# scu_board.net
KiCad netlist of a schematic drawn in EAGLE
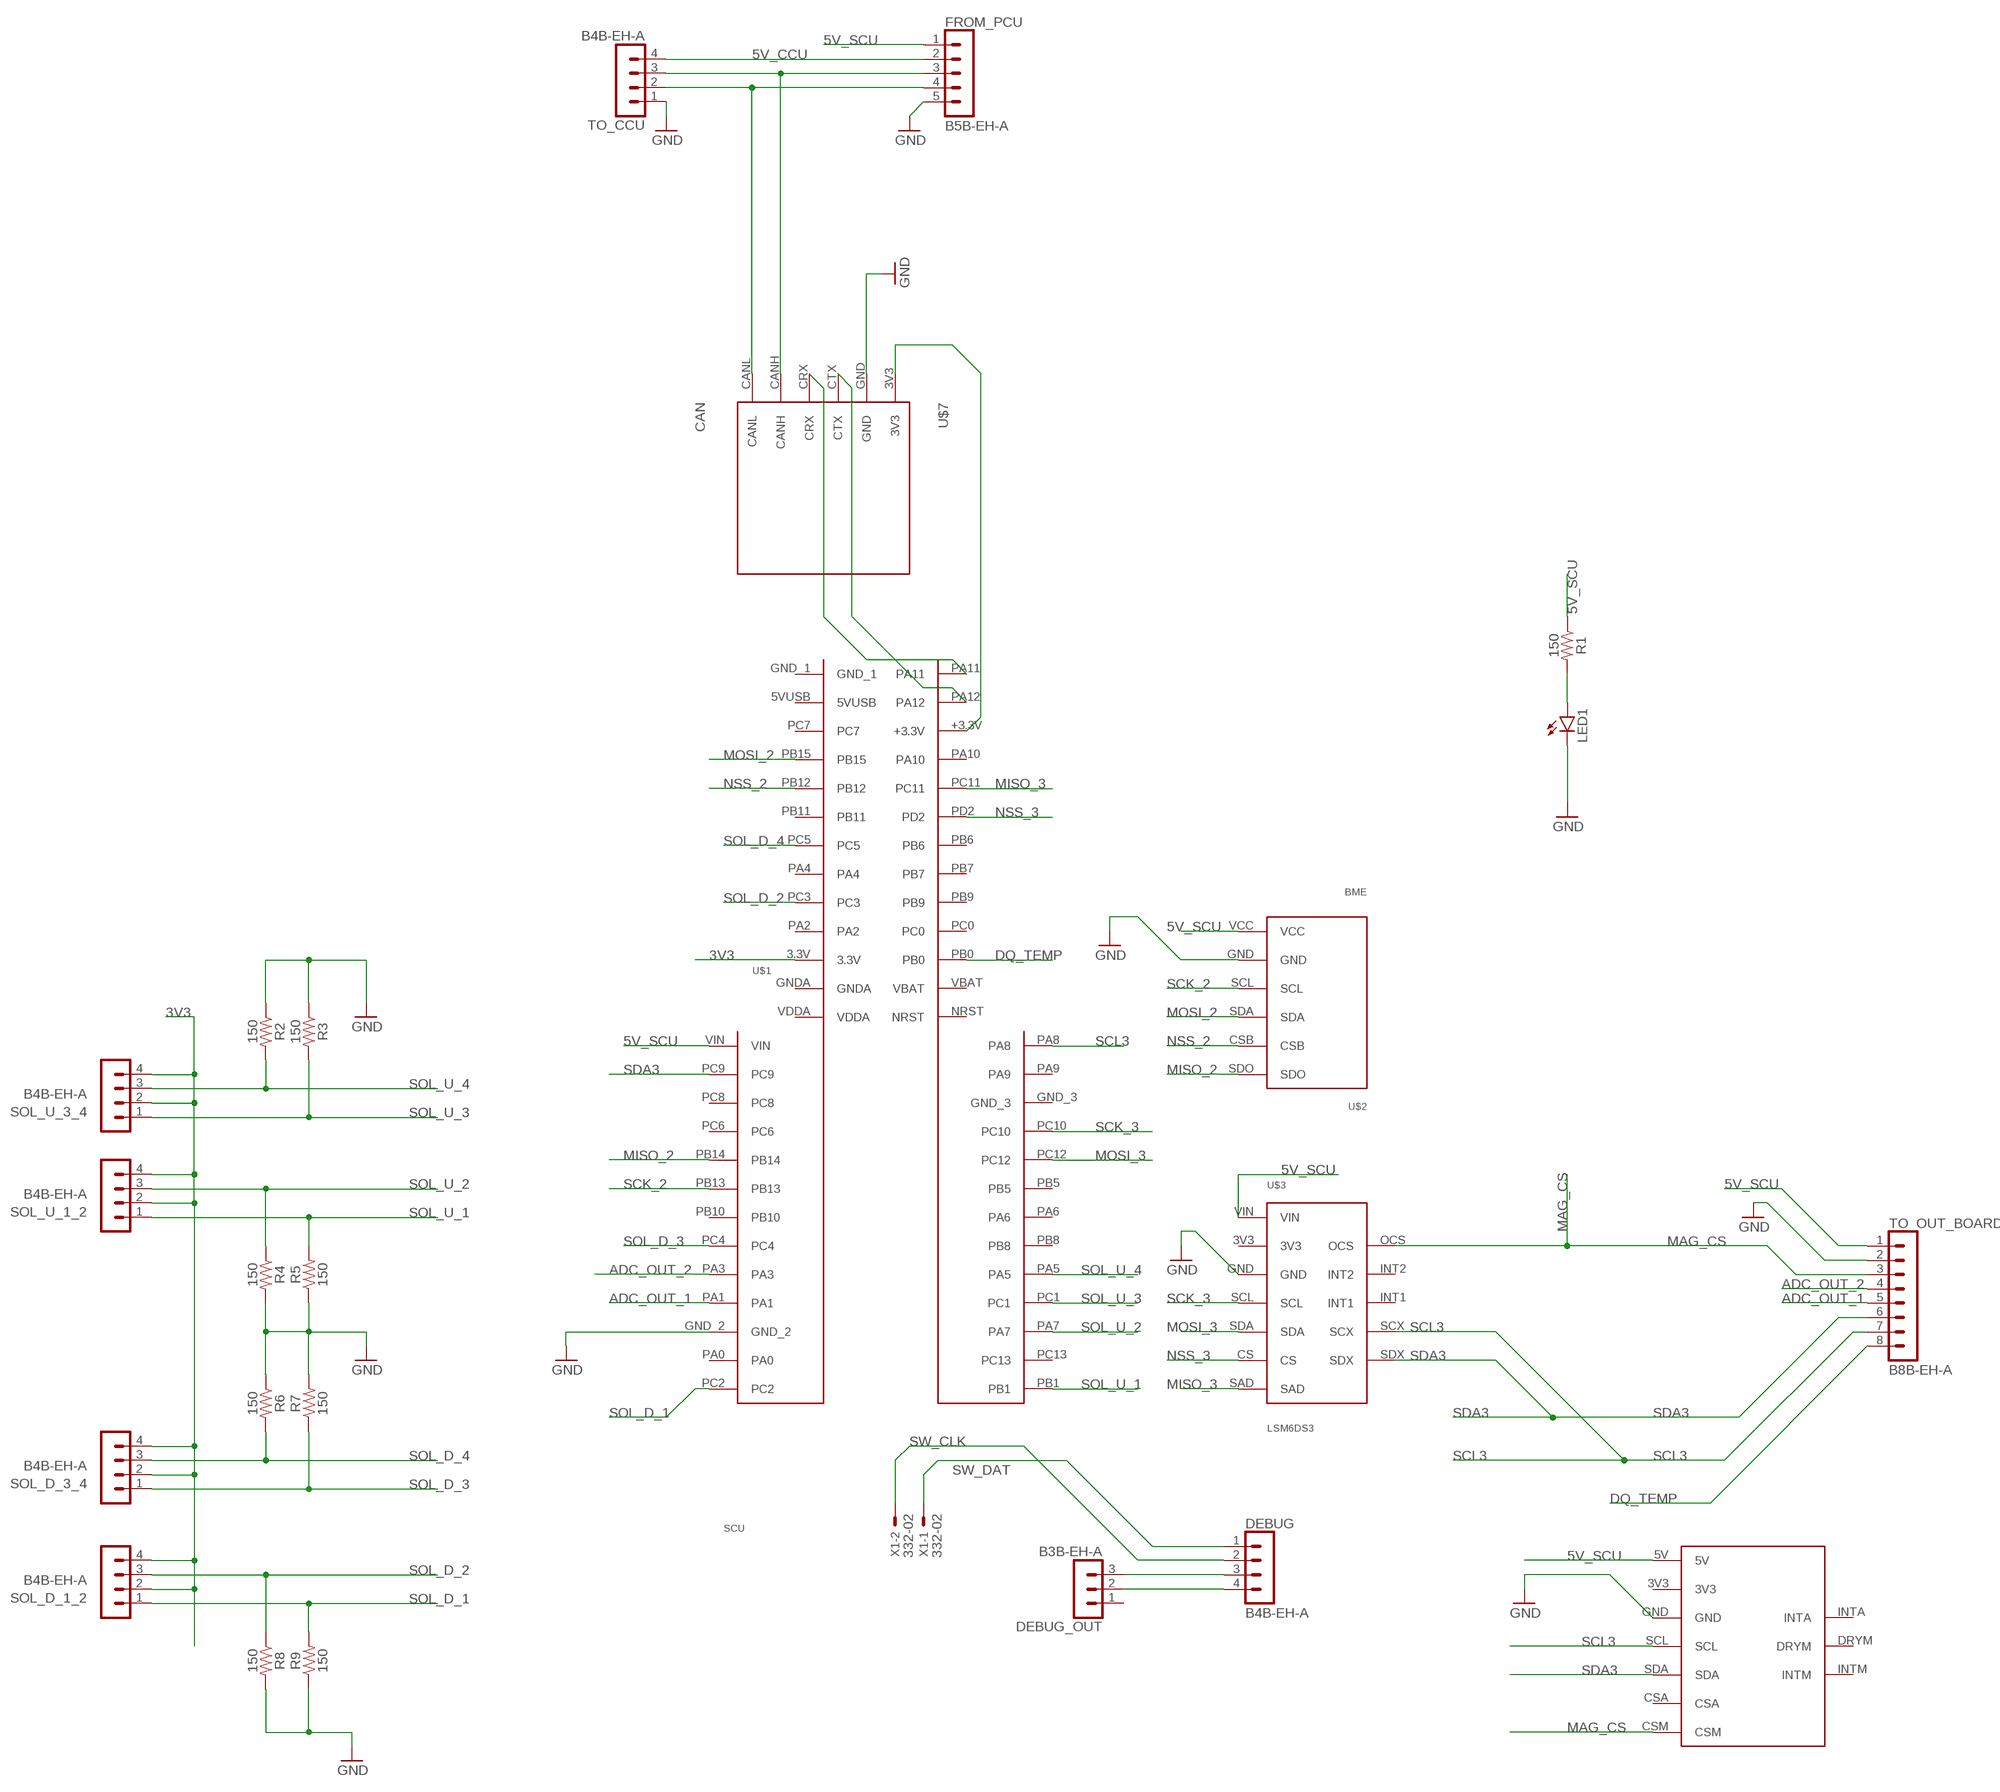
[diagram p0: schematic, sheet 1]

(export (version "E")
  (design (tool "Eeschema 10.0.6"))
  (components
    (comp (ref "DEBUG")
      (value "B4B-EH-A")
      (footprint "eagle-import:B4B-EH-A")
      (libsource (lib "eagle-import") (part "B4B-EH-A"))
    )
    (comp (ref "DEBUG_OUT")
      (value "B3B-EH-A")
      (footprint "eagle-import:B3B-EH-A")
      (libsource (lib "eagle-import") (part "B3B-EH-A"))
    )
    (comp (ref "FROM_PCU")
      (value "B5B-EH-A")
      (footprint "eagle-import:B5B-EH-A")
      (libsource (lib "eagle-import") (part "B5B-EH-A"))
    )
    (comp (ref "LED1")
      (value "LED5MM")
      (footprint "eagle-import:LED5MM")
      (libsource (lib "eagle-import") (part "LED5MM"))
    )
    (comp (ref "R1")
      (value "150")
      (footprint "eagle-import:AXIAL-0.3")
      (libsource (lib "eagle-import") (part "RESISTORAXIAL-0.3"))
    )
    (comp (ref "R2")
      (value "150")
      (footprint "eagle-import:AXIAL-0.3")
      (libsource (lib "eagle-import") (part "RESISTORAXIAL-0.3"))
    )
    (comp (ref "R3")
      (value "150")
      (footprint "eagle-import:AXIAL-0.3")
      (libsource (lib "eagle-import") (part "RESISTORAXIAL-0.3"))
    )
    (comp (ref "R4")
      (value "150")
      (footprint "eagle-import:AXIAL-0.3")
      (libsource (lib "eagle-import") (part "RESISTORAXIAL-0.3"))
    )
    (comp (ref "R5")
      (value "150")
      (footprint "eagle-import:AXIAL-0.3")
      (libsource (lib "eagle-import") (part "RESISTORAXIAL-0.3"))
    )
    (comp (ref "R6")
      (value "150")
      (footprint "eagle-import:AXIAL-0.3")
      (libsource (lib "eagle-import") (part "RESISTORAXIAL-0.3"))
    )
    (comp (ref "R7")
      (value "150")
      (footprint "eagle-import:AXIAL-0.3")
      (libsource (lib "eagle-import") (part "RESISTORAXIAL-0.3"))
    )
    (comp (ref "R8")
      (value "150")
      (footprint "eagle-import:AXIAL-0.3")
      (libsource (lib "eagle-import") (part "RESISTORAXIAL-0.3"))
    )
    (comp (ref "R9")
      (value "150")
      (footprint "eagle-import:AXIAL-0.3")
      (libsource (lib "eagle-import") (part "RESISTORAXIAL-0.3"))
    )
    (comp (ref "SOL_D_1_2")
      (value "B4B-EH-A")
      (footprint "eagle-import:B4B-EH-A")
      (libsource (lib "eagle-import") (part "B4B-EH-A"))
    )
    (comp (ref "SOL_D_3_4")
      (value "B4B-EH-A")
      (footprint "eagle-import:B4B-EH-A")
      (libsource (lib "eagle-import") (part "B4B-EH-A"))
    )
    (comp (ref "SOL_U_1_2")
      (value "B4B-EH-A")
      (footprint "eagle-import:B4B-EH-A")
      (libsource (lib "eagle-import") (part "B4B-EH-A"))
    )
    (comp (ref "SOL_U_3_4")
      (value "B4B-EH-A")
      (footprint "eagle-import:B4B-EH-A")
      (libsource (lib "eagle-import") (part "B4B-EH-A"))
    )
    (comp (ref "TO_CCU")
      (value "B4B-EH-A")
      (footprint "eagle-import:B4B-EH-A")
      (libsource (lib "eagle-import") (part "B4B-EH-A"))
    )
    (comp (ref "TO_OUT_BOARD")
      (value "B8B-EH-A")
      (footprint "eagle-import:B8B-EH-A")
      (libsource (lib "eagle-import") (part "B8B-EH-A"))
    )
    (comp (ref "U$1")
      (value "SCU")
      (footprint "eagle-import:SCU")
      (libsource (lib "eagle-import") (part "SCU"))
    )
    (comp (ref "U$2")
      (value "BME")
      (footprint "eagle-import:BME")
      (libsource (lib "eagle-import") (part "BME"))
    )
    (comp (ref "U$3")
      (value "LSM6DS3")
      (footprint "eagle-import:LSM6DS3")
      (libsource (lib "eagle-import") (part "LSM6DS3"))
    )
    (comp (ref "U$4")
      (value "LSM303C")
      (footprint "eagle-import:LSM303C")
      (libsource (lib "eagle-import") (part "LSM303C"))
    )
    (comp (ref "U$7")
      (value "CAN")
      (footprint "eagle-import:CAN")
      (libsource (lib "eagle-import") (part "CAN"))
    )
    (comp (ref "X1")
      (value "332-02")
      (footprint "eagle-import:332-02")
      (libsource (lib "eagle-import") (part "332-02"))
    )
  )
  (nets
    (net (code "1") (name "/3V3") (class "Default")
      (node (ref "SOL_D_1_2") (pin "2") (pinfunction "2_2") (pintype "passive"))
      (node (ref "SOL_D_1_2") (pin "4") (pinfunction "4_4") (pintype "passive"))
      (node (ref "SOL_D_3_4") (pin "2") (pinfunction "2_2") (pintype "passive"))
      (node (ref "SOL_D_3_4") (pin "4") (pinfunction "4_4") (pintype "passive"))
      (node (ref "SOL_U_1_2") (pin "2") (pinfunction "2_2") (pintype "passive"))
      (node (ref "SOL_U_1_2") (pin "4") (pinfunction "4_4") (pintype "passive"))
      (node (ref "SOL_U_3_4") (pin "2") (pinfunction "2_2") (pintype "passive"))
      (node (ref "SOL_U_3_4") (pin "4") (pinfunction "4_4") (pintype "passive"))
      (node (ref "U$1") (pin "3.3V") (pinfunction "3.3V_3.3V") (pintype "bidirectional"))
    )
    (net (code "2") (name "/5V_CCU") (class "Default")
      (node (ref "FROM_PCU") (pin "2") (pinfunction "2_2") (pintype "passive"))
      (node (ref "TO_CCU") (pin "4") (pinfunction "4_4") (pintype "passive"))
    )
    (net (code "3") (name "/5V_SCU") (class "Default")
      (node (ref "FROM_PCU") (pin "1") (pinfunction "1_1") (pintype "passive"))
      (node (ref "R1") (pin "P$1") (pinfunction "1_P$1") (pintype "passive"))
      (node (ref "TO_OUT_BOARD") (pin "1") (pinfunction "1_1") (pintype "passive"))
      (node (ref "U$1") (pin "VIN") (pinfunction "VIN_VIN") (pintype "bidirectional"))
      (node (ref "U$2") (pin "VCC") (pinfunction "VCC_VCC") (pintype "bidirectional"))
      (node (ref "U$3") (pin "VIN") (pinfunction "VIN_VIN") (pintype "bidirectional"))
      (node (ref "U$4") (pin "5V") (pinfunction "5V_5V") (pintype "bidirectional"))
    )
    (net (code "4") (name "/ADC_OUT_1") (class "Default")
      (node (ref "TO_OUT_BOARD") (pin "5") (pinfunction "5_5") (pintype "passive"))
      (node (ref "U$1") (pin "PA1") (pinfunction "PA1_PA1") (pintype "bidirectional"))
    )
    (net (code "5") (name "/ADC_OUT_2") (class "Default")
      (node (ref "TO_OUT_BOARD") (pin "4") (pinfunction "4_4") (pintype "passive"))
      (node (ref "U$1") (pin "PA3") (pinfunction "PA3_PA3") (pintype "bidirectional"))
    )
    (net (code "6") (name "/DQ_TEMP") (class "Default")
      (node (ref "TO_OUT_BOARD") (pin "8") (pinfunction "8_8") (pintype "passive"))
      (node (ref "U$1") (pin "PB0") (pinfunction "PB0_PB0") (pintype "bidirectional"))
    )
    (net (code "7") (name "/MAG_CS") (class "Default")
      (node (ref "TO_OUT_BOARD") (pin "3") (pinfunction "3_3") (pintype "passive"))
      (node (ref "U$3") (pin "OCS") (pinfunction "OCS_OCS") (pintype "bidirectional"))
      (node (ref "U$4") (pin "CSM") (pinfunction "CSM_CSM") (pintype "bidirectional"))
    )
    (net (code "8") (name "/MISO_2") (class "Default")
      (node (ref "U$1") (pin "PB14") (pinfunction "PB14_PB14") (pintype "bidirectional"))
      (node (ref "U$2") (pin "SDO") (pinfunction "SDO_SDO") (pintype "bidirectional"))
    )
    (net (code "9") (name "/MISO_3") (class "Default")
      (node (ref "U$1") (pin "PC11") (pinfunction "PC11_PC11") (pintype "bidirectional"))
      (node (ref "U$3") (pin "SAD") (pinfunction "SAD_SAD") (pintype "bidirectional"))
    )
    (net (code "10") (name "/MOSI_2") (class "Default")
      (node (ref "U$1") (pin "PB15") (pinfunction "PB15_PB15") (pintype "bidirectional"))
      (node (ref "U$2") (pin "SDA") (pinfunction "SDA_SDA") (pintype "bidirectional"))
    )
    (net (code "11") (name "/MOSI_3") (class "Default")
      (node (ref "U$1") (pin "PC12") (pinfunction "PC12_PC12") (pintype "bidirectional"))
      (node (ref "U$3") (pin "SDA") (pinfunction "SDA_SDA") (pintype "bidirectional"))
    )
    (net (code "12") (name "/NSS_2") (class "Default")
      (node (ref "U$1") (pin "PB12") (pinfunction "PB12_PB12") (pintype "bidirectional"))
      (node (ref "U$2") (pin "CSB") (pinfunction "CSB_CSB") (pintype "bidirectional"))
    )
    (net (code "13") (name "/NSS_3") (class "Default")
      (node (ref "U$1") (pin "PD2") (pinfunction "PD2_PD2") (pintype "bidirectional"))
      (node (ref "U$3") (pin "CS") (pinfunction "CS_CS") (pintype "bidirectional"))
    )
    (net (code "14") (name "/SCK_2") (class "Default")
      (node (ref "U$1") (pin "PB13") (pinfunction "PB13_PB13") (pintype "bidirectional"))
      (node (ref "U$2") (pin "SCL") (pinfunction "SCL_SCL") (pintype "bidirectional"))
    )
    (net (code "15") (name "/SCK_3") (class "Default")
      (node (ref "U$1") (pin "PC10") (pinfunction "PC10_PC10") (pintype "bidirectional"))
      (node (ref "U$3") (pin "SCL") (pinfunction "SCL_SCL") (pintype "bidirectional"))
    )
    (net (code "16") (name "/SCL3") (class "Default")
      (node (ref "TO_OUT_BOARD") (pin "7") (pinfunction "7_7") (pintype "passive"))
      (node (ref "U$1") (pin "PA8") (pinfunction "PA8_PA8") (pintype "bidirectional"))
      (node (ref "U$3") (pin "SCX") (pinfunction "SCX_SCX") (pintype "bidirectional"))
      (node (ref "U$4") (pin "SCL") (pinfunction "SCL_SCL") (pintype "bidirectional"))
    )
    (net (code "17") (name "/SDA3") (class "Default")
      (node (ref "TO_OUT_BOARD") (pin "6") (pinfunction "6_6") (pintype "passive"))
      (node (ref "U$1") (pin "PC9") (pinfunction "PC9_PC9") (pintype "bidirectional"))
      (node (ref "U$3") (pin "SDX") (pinfunction "SDX_SDX") (pintype "bidirectional"))
      (node (ref "U$4") (pin "SDA") (pinfunction "SDA_SDA") (pintype "bidirectional"))
    )
    (net (code "18") (name "/SOL_D_1") (class "Default")
      (node (ref "R9") (pin "P$2") (pinfunction "2_P$2") (pintype "passive"))
      (node (ref "SOL_D_1_2") (pin "1") (pinfunction "1_1") (pintype "passive"))
      (node (ref "U$1") (pin "PC2") (pinfunction "PC2_PC2") (pintype "bidirectional"))
    )
    (net (code "19") (name "/SOL_D_2") (class "Default")
      (node (ref "R8") (pin "P$1") (pinfunction "1_P$1") (pintype "passive"))
      (node (ref "SOL_D_1_2") (pin "3") (pinfunction "3_3") (pintype "passive"))
      (node (ref "U$1") (pin "PC3") (pinfunction "PC3_PC3") (pintype "bidirectional"))
    )
    (net (code "20") (name "/SOL_D_3") (class "Default")
      (node (ref "R7") (pin "P$1") (pinfunction "1_P$1") (pintype "passive"))
      (node (ref "SOL_D_3_4") (pin "1") (pinfunction "1_1") (pintype "passive"))
      (node (ref "U$1") (pin "PC4") (pinfunction "PC4_PC4") (pintype "bidirectional"))
    )
    (net (code "21") (name "/SOL_D_4") (class "Default")
      (node (ref "R6") (pin "P$2") (pinfunction "2_P$2") (pintype "passive"))
      (node (ref "SOL_D_3_4") (pin "3") (pinfunction "3_3") (pintype "passive"))
      (node (ref "U$1") (pin "PC5") (pinfunction "PC5_PC5") (pintype "bidirectional"))
    )
    (net (code "22") (name "/SOL_U_1") (class "Default")
      (node (ref "R5") (pin "P$2") (pinfunction "2_P$2") (pintype "passive"))
      (node (ref "SOL_U_1_2") (pin "1") (pinfunction "1_1") (pintype "passive"))
      (node (ref "U$1") (pin "PB1") (pinfunction "PB1_PB1") (pintype "bidirectional"))
    )
    (net (code "23") (name "/SOL_U_2") (class "Default")
      (node (ref "R4") (pin "P$1") (pinfunction "1_P$1") (pintype "passive"))
      (node (ref "SOL_U_1_2") (pin "3") (pinfunction "3_3") (pintype "passive"))
      (node (ref "U$1") (pin "PA7") (pinfunction "PA7_PA7") (pintype "bidirectional"))
    )
    (net (code "24") (name "/SOL_U_3") (class "Default")
      (node (ref "R3") (pin "P$2") (pinfunction "2_P$2") (pintype "passive"))
      (node (ref "SOL_U_3_4") (pin "1") (pinfunction "1_1") (pintype "passive"))
      (node (ref "U$1") (pin "PC1") (pinfunction "PC1_PC1") (pintype "bidirectional"))
    )
    (net (code "25") (name "/SOL_U_4") (class "Default")
      (node (ref "R2") (pin "P$2") (pinfunction "2_P$2") (pintype "passive"))
      (node (ref "SOL_U_3_4") (pin "3") (pinfunction "3_3") (pintype "passive"))
      (node (ref "U$1") (pin "PA5") (pinfunction "PA5_PA5") (pintype "bidirectional"))
    )
    (net (code "26") (name "/SW_CLK") (class "Default")
      (node (ref "DEBUG") (pin "2") (pinfunction "2_2") (pintype "passive"))
      (node (ref "X1") (pin "2") (pinfunction "S_2") (pintype "passive"))
    )
    (net (code "27") (name "/SW_DAT") (class "Default")
      (node (ref "DEBUG") (pin "1") (pinfunction "1_1") (pintype "passive"))
      (node (ref "X1") (pin "1") (pinfunction "S_1") (pintype "passive"))
    )
    (net (code "28") (name "GND") (class "Default")
      (node (ref "FROM_PCU") (pin "5") (pinfunction "5_5") (pintype "passive"))
      (node (ref "LED1") (pin "K") (pinfunction "C_K") (pintype "passive"))
      (node (ref "R2") (pin "P$1") (pinfunction "1_P$1") (pintype "passive"))
      (node (ref "R3") (pin "P$1") (pinfunction "1_P$1") (pintype "passive"))
      (node (ref "R4") (pin "P$2") (pinfunction "2_P$2") (pintype "passive"))
      (node (ref "R5") (pin "P$1") (pinfunction "1_P$1") (pintype "passive"))
      (node (ref "R6") (pin "P$1") (pinfunction "1_P$1") (pintype "passive"))
      (node (ref "R7") (pin "P$2") (pinfunction "2_P$2") (pintype "passive"))
      (node (ref "R8") (pin "P$2") (pinfunction "2_P$2") (pintype "passive"))
      (node (ref "R9") (pin "P$1") (pinfunction "1_P$1") (pintype "passive"))
      (node (ref "TO_CCU") (pin "1") (pinfunction "1_1") (pintype "passive"))
      (node (ref "TO_OUT_BOARD") (pin "2") (pinfunction "2_2") (pintype "passive"))
      (node (ref "U$1") (pin "GND_2") (pinfunction "GND_2_GND_2") (pintype "bidirectional"))
      (node (ref "U$2") (pin "GND") (pinfunction "GND_GND") (pintype "bidirectional"))
      (node (ref "U$3") (pin "GND") (pinfunction "GND_GND") (pintype "bidirectional"))
      (node (ref "U$4") (pin "GND") (pinfunction "GND_GND") (pintype "bidirectional"))
      (node (ref "U$7") (pin "GND") (pinfunction "GND_GND") (pintype "bidirectional"))
    )
    (net (code "29") (name "Net-(DEBUG-Pad3)") (class "Default")
      (node (ref "DEBUG") (pin "3") (pinfunction "3_3") (pintype "passive"))
      (node (ref "DEBUG_OUT") (pin "3") (pinfunction "3_3") (pintype "passive"))
    )
    (net (code "30") (name "Net-(DEBUG-Pad4)") (class "Default")
      (node (ref "DEBUG") (pin "4") (pinfunction "4_4") (pintype "passive"))
      (node (ref "DEBUG_OUT") (pin "2") (pinfunction "2_2") (pintype "passive"))
    )
    (net (code "31") (name "Net-(FROM_PCU-Pad3)") (class "Default")
      (node (ref "FROM_PCU") (pin "3") (pinfunction "3_3") (pintype "passive"))
      (node (ref "TO_CCU") (pin "3") (pinfunction "3_3") (pintype "passive"))
      (node (ref "U$7") (pin "CANH") (pinfunction "CANH_CANH") (pintype "bidirectional"))
    )
    (net (code "32") (name "Net-(FROM_PCU-Pad4)") (class "Default")
      (node (ref "FROM_PCU") (pin "4") (pinfunction "4_4") (pintype "passive"))
      (node (ref "TO_CCU") (pin "2") (pinfunction "2_2") (pintype "passive"))
      (node (ref "U$7") (pin "CANL") (pinfunction "CANL_CANL") (pintype "bidirectional"))
    )
    (net (code "33") (name "Net-(R1-2)") (class "Default")
      (node (ref "LED1") (pin "A") (pinfunction "A_A") (pintype "passive"))
      (node (ref "R1") (pin "P$2") (pinfunction "2_P$2") (pintype "passive"))
    )
    (net (code "34") (name "Net-(U$1-Pad+3.3V)") (class "Default")
      (node (ref "U$1") (pin "+3.3V") (pinfunction "+3.3V_+3.3V") (pintype "bidirectional"))
      (node (ref "U$7") (pin "3V3") (pinfunction "3V3_3V3") (pintype "bidirectional"))
    )
    (net (code "35") (name "Net-(U$1-PadPA11)") (class "Default")
      (node (ref "U$1") (pin "PA11") (pinfunction "PA11_PA11") (pintype "bidirectional"))
      (node (ref "U$7") (pin "CRX") (pinfunction "CRX_CRX") (pintype "bidirectional"))
    )
    (net (code "36") (name "Net-(U$1-PadPA12)") (class "Default")
      (node (ref "U$1") (pin "PA12") (pinfunction "PA12_PA12") (pintype "bidirectional"))
      (node (ref "U$7") (pin "CTX") (pinfunction "CTX_CTX") (pintype "bidirectional"))
    )
    (net (code "37") (name "unconnected-(DEBUG_OUT-Pad1)") (class "Default")
      (node (ref "DEBUG_OUT") (pin "1") (pinfunction "1_1") (pintype "passive"))
    )
    (net (code "38") (name "unconnected-(U$1-Pad5VUSB)") (class "Default")
      (node (ref "U$1") (pin "5VUSB") (pinfunction "5VUSB_5VUSB") (pintype "bidirectional"))
    )
    (net (code "39") (name "unconnected-(U$1-PadGNDA)") (class "Default")
      (node (ref "U$1") (pin "GNDA") (pinfunction "GNDA_GNDA") (pintype "bidirectional"))
    )
    (net (code "40") (name "unconnected-(U$1-PadGND_1)") (class "Default")
      (node (ref "U$1") (pin "GND_1") (pinfunction "GND_1_GND_1") (pintype "bidirectional"))
    )
    (net (code "41") (name "unconnected-(U$1-PadGND_3)") (class "Default")
      (node (ref "U$1") (pin "GND_3") (pinfunction "GND_3_GND_3") (pintype "bidirectional"))
    )
    (net (code "42") (name "unconnected-(U$1-PadNRST)") (class "Default")
      (node (ref "U$1") (pin "NRST") (pinfunction "NRST_NRST") (pintype "bidirectional"))
    )
    (net (code "43") (name "unconnected-(U$1-PadPA0)") (class "Default")
      (node (ref "U$1") (pin "PA0") (pinfunction "PA0_PA0") (pintype "bidirectional"))
    )
    (net (code "44") (name "unconnected-(U$1-PadPA2)") (class "Default")
      (node (ref "U$1") (pin "PA2") (pinfunction "PA2_PA2") (pintype "bidirectional"))
    )
    (net (code "45") (name "unconnected-(U$1-PadPA4)") (class "Default")
      (node (ref "U$1") (pin "PA4") (pinfunction "PA4_PA4") (pintype "bidirectional"))
    )
    (net (code "46") (name "unconnected-(U$1-PadPA6)") (class "Default")
      (node (ref "U$1") (pin "PA6") (pinfunction "PA6_PA6") (pintype "bidirectional"))
    )
    (net (code "47") (name "unconnected-(U$1-PadPA9)") (class "Default")
      (node (ref "U$1") (pin "PA9") (pinfunction "PA9_PA9") (pintype "bidirectional"))
    )
    (net (code "48") (name "unconnected-(U$1-PadPA10)") (class "Default")
      (node (ref "U$1") (pin "PA10") (pinfunction "PA10_PA10") (pintype "bidirectional"))
    )
    (net (code "49") (name "unconnected-(U$1-PadPB5)") (class "Default")
      (node (ref "U$1") (pin "PB5") (pinfunction "PB5_PB5") (pintype "bidirectional"))
    )
    (net (code "50") (name "unconnected-(U$1-PadPB6)") (class "Default")
      (node (ref "U$1") (pin "PB6") (pinfunction "PB6_PB6") (pintype "bidirectional"))
    )
    (net (code "51") (name "unconnected-(U$1-PadPB7)") (class "Default")
      (node (ref "U$1") (pin "PB7") (pinfunction "PB7_PB7") (pintype "bidirectional"))
    )
    (net (code "52") (name "unconnected-(U$1-PadPB8)") (class "Default")
      (node (ref "U$1") (pin "PB8") (pinfunction "PB8_PB8") (pintype "bidirectional"))
    )
    (net (code "53") (name "unconnected-(U$1-PadPB9)") (class "Default")
      (node (ref "U$1") (pin "PB9") (pinfunction "PB9_PB9") (pintype "bidirectional"))
    )
    (net (code "54") (name "unconnected-(U$1-PadPB10)") (class "Default")
      (node (ref "U$1") (pin "PB10") (pinfunction "PB10_PB10") (pintype "bidirectional"))
    )
    (net (code "55") (name "unconnected-(U$1-PadPB11)") (class "Default")
      (node (ref "U$1") (pin "PB11") (pinfunction "PB11_PB11") (pintype "bidirectional"))
    )
    (net (code "56") (name "unconnected-(U$1-PadPC0)") (class "Default")
      (node (ref "U$1") (pin "PC0") (pinfunction "PC0_PC0") (pintype "bidirectional"))
    )
    (net (code "57") (name "unconnected-(U$1-PadPC6)") (class "Default")
      (node (ref "U$1") (pin "PC6") (pinfunction "PC6_PC6") (pintype "bidirectional"))
    )
    (net (code "58") (name "unconnected-(U$1-PadPC7)") (class "Default")
      (node (ref "U$1") (pin "PC7") (pinfunction "PC7_PC7") (pintype "bidirectional"))
    )
    (net (code "59") (name "unconnected-(U$1-PadPC8)") (class "Default")
      (node (ref "U$1") (pin "PC8") (pinfunction "PC8_PC8") (pintype "bidirectional"))
    )
    (net (code "60") (name "unconnected-(U$1-PadPC13)") (class "Default")
      (node (ref "U$1") (pin "PC13") (pinfunction "PC13_PC13") (pintype "bidirectional"))
    )
    (net (code "61") (name "unconnected-(U$1-PadVBAT)") (class "Default")
      (node (ref "U$1") (pin "VBAT") (pinfunction "VBAT_VBAT") (pintype "bidirectional"))
    )
    (net (code "62") (name "unconnected-(U$1-PadVDDA)") (class "Default")
      (node (ref "U$1") (pin "VDDA") (pinfunction "VDDA_VDDA") (pintype "bidirectional"))
    )
    (net (code "63") (name "unconnected-(U$3-Pad3V3)") (class "Default")
      (node (ref "U$3") (pin "3V3") (pinfunction "3V3_3V3") (pintype "bidirectional"))
    )
    (net (code "64") (name "unconnected-(U$3-PadINT1)") (class "Default")
      (node (ref "U$3") (pin "INT1") (pinfunction "INT1_INT1") (pintype "bidirectional"))
    )
    (net (code "65") (name "unconnected-(U$3-PadINT2)") (class "Default")
      (node (ref "U$3") (pin "INT2") (pinfunction "INT2_INT2") (pintype "bidirectional"))
    )
    (net (code "66") (name "unconnected-(U$4-Pad3V3)") (class "Default")
      (node (ref "U$4") (pin "3V3") (pinfunction "3V3_3V3") (pintype "bidirectional"))
    )
    (net (code "67") (name "unconnected-(U$4-PadCSA)") (class "Default")
      (node (ref "U$4") (pin "CSA") (pinfunction "CSA_CSA") (pintype "bidirectional"))
    )
    (net (code "68") (name "unconnected-(U$4-PadDRYM)") (class "Default")
      (node (ref "U$4") (pin "DRYM") (pinfunction "DRYM_DRYM") (pintype "bidirectional"))
    )
    (net (code "69") (name "unconnected-(U$4-PadINTA)") (class "Default")
      (node (ref "U$4") (pin "INTA") (pinfunction "INTA_INTA") (pintype "bidirectional"))
    )
    (net (code "70") (name "unconnected-(U$4-PadINTM)") (class "Default")
      (node (ref "U$4") (pin "INTM") (pinfunction "INTM_INTM") (pintype "bidirectional"))
    )
  )
)
